# Dashboard_rev4.net
KiCad netlist of a schematic drawn in EAGLE
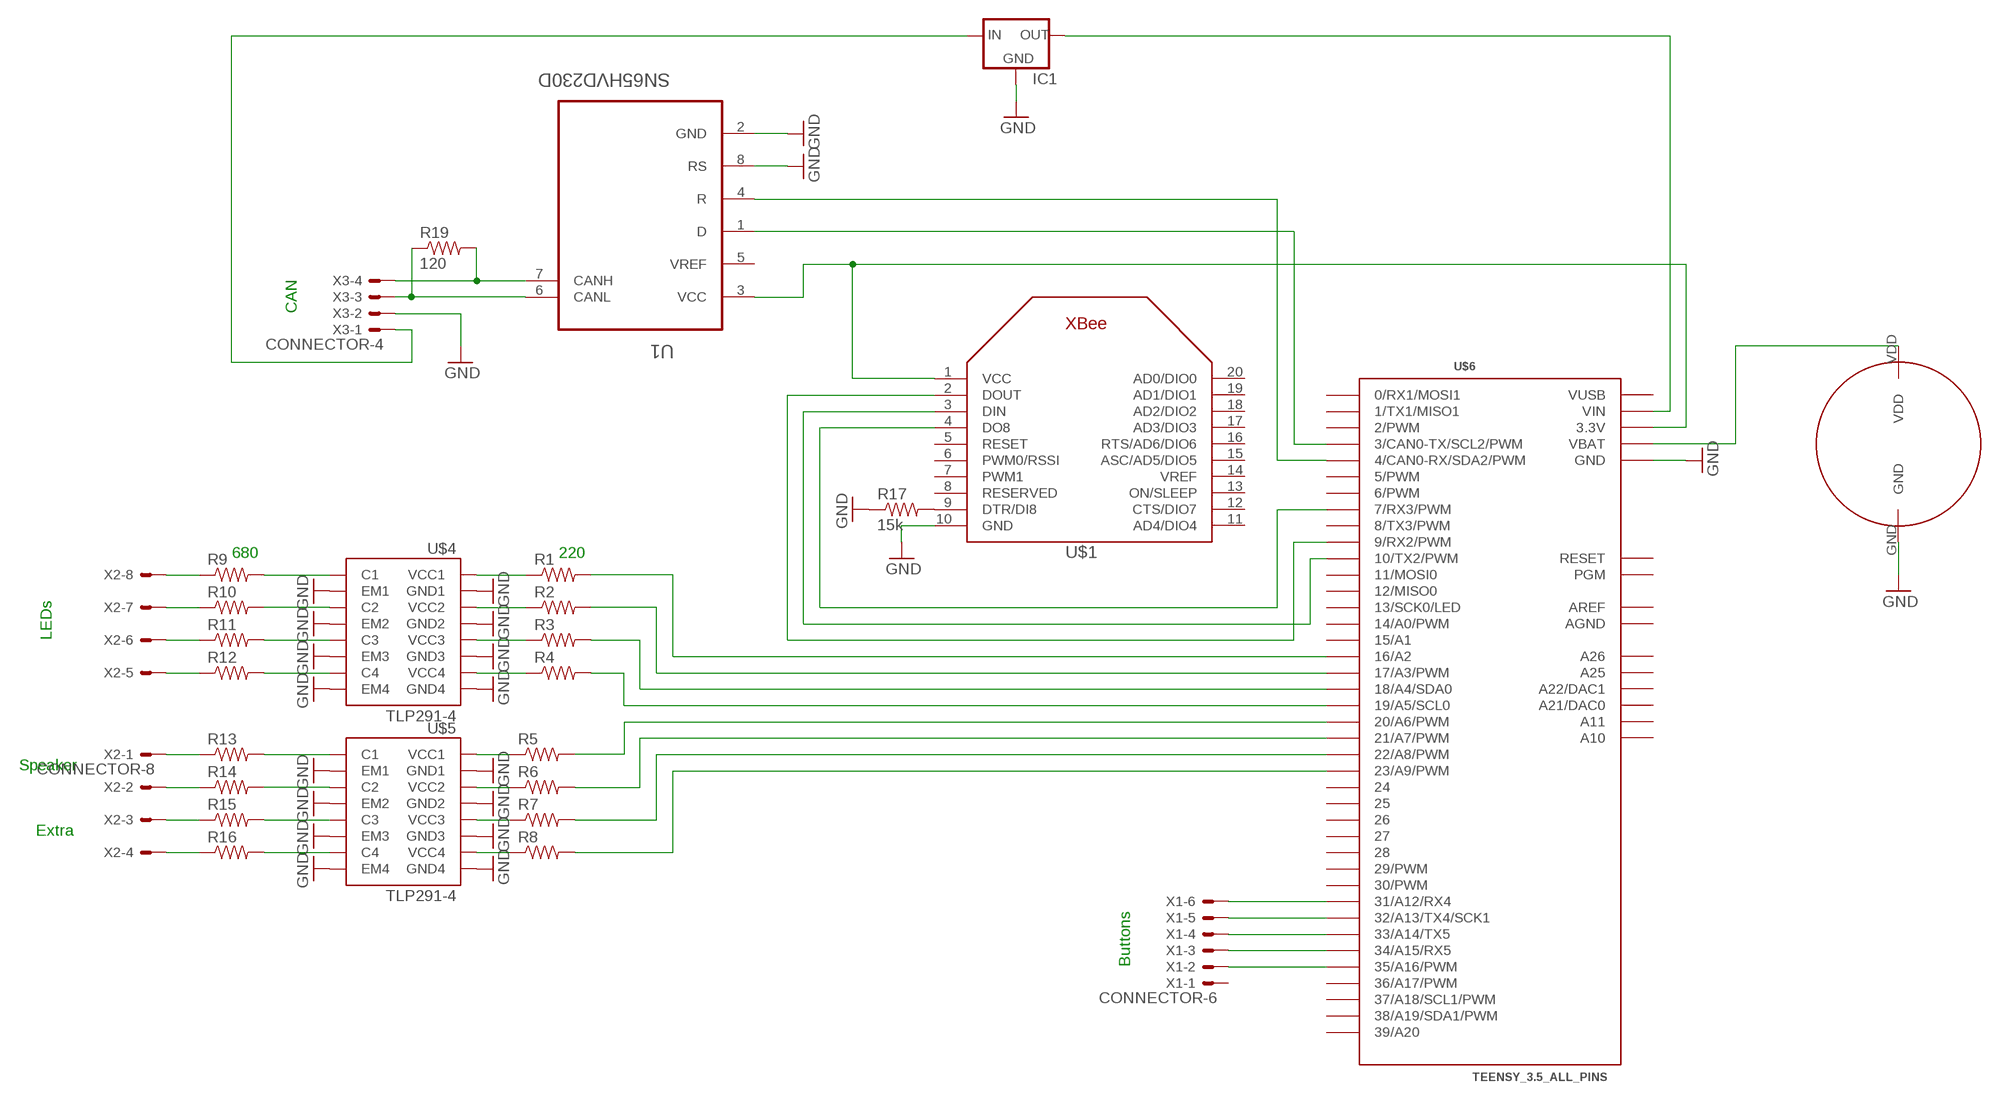
[diagram p0: schematic, sheet 1]

(export (version "E")
  (design (tool "Eeschema 10.0.6"))
  (components
    (comp (ref "IC1")
      (value "5VREG_L7805SPACED")
      (footprint "eagle-import:TO-220-SPACED")
      (libsource (lib "eagle-import") (part "5VREG_L7805SPACED"))
    )
    (comp (ref "R1")
      (value "RESISTORAXIAL-0.3")
      (footprint "eagle-import:AXIAL-0.3")
      (libsource (lib "eagle-import") (part "RESISTORAXIAL-0.3"))
    )
    (comp (ref "R2")
      (value "RESISTORAXIAL-0.3")
      (footprint "eagle-import:AXIAL-0.3")
      (libsource (lib "eagle-import") (part "RESISTORAXIAL-0.3"))
    )
    (comp (ref "R3")
      (value "RESISTORAXIAL-0.3")
      (footprint "eagle-import:AXIAL-0.3")
      (libsource (lib "eagle-import") (part "RESISTORAXIAL-0.3"))
    )
    (comp (ref "R4")
      (value "RESISTORAXIAL-0.3")
      (footprint "eagle-import:AXIAL-0.3")
      (libsource (lib "eagle-import") (part "RESISTORAXIAL-0.3"))
    )
    (comp (ref "R5")
      (value "RESISTORAXIAL-0.3")
      (footprint "eagle-import:AXIAL-0.3")
      (libsource (lib "eagle-import") (part "RESISTORAXIAL-0.3"))
    )
    (comp (ref "R6")
      (value "RESISTORAXIAL-0.3")
      (footprint "eagle-import:AXIAL-0.3")
      (libsource (lib "eagle-import") (part "RESISTORAXIAL-0.3"))
    )
    (comp (ref "R7")
      (value "RESISTORAXIAL-0.3")
      (footprint "eagle-import:AXIAL-0.3")
      (libsource (lib "eagle-import") (part "RESISTORAXIAL-0.3"))
    )
    (comp (ref "R8")
      (value "RESISTORAXIAL-0.3")
      (footprint "eagle-import:AXIAL-0.3")
      (libsource (lib "eagle-import") (part "RESISTORAXIAL-0.3"))
    )
    (comp (ref "R9")
      (value "RESISTORAXIAL-0.3")
      (footprint "eagle-import:AXIAL-0.3")
      (libsource (lib "eagle-import") (part "RESISTORAXIAL-0.3"))
    )
    (comp (ref "R10")
      (value "RESISTORAXIAL-0.3")
      (footprint "eagle-import:AXIAL-0.3")
      (libsource (lib "eagle-import") (part "RESISTORAXIAL-0.3"))
    )
    (comp (ref "R11")
      (value "RESISTORAXIAL-0.3")
      (footprint "eagle-import:AXIAL-0.3")
      (libsource (lib "eagle-import") (part "RESISTORAXIAL-0.3"))
    )
    (comp (ref "R12")
      (value "RESISTORAXIAL-0.3")
      (footprint "eagle-import:AXIAL-0.3")
      (libsource (lib "eagle-import") (part "RESISTORAXIAL-0.3"))
    )
    (comp (ref "R13")
      (value "RESISTORAXIAL-0.3")
      (footprint "eagle-import:AXIAL-0.3")
      (libsource (lib "eagle-import") (part "RESISTORAXIAL-0.3"))
    )
    (comp (ref "R14")
      (value "RESISTORAXIAL-0.3")
      (footprint "eagle-import:AXIAL-0.3")
      (libsource (lib "eagle-import") (part "RESISTORAXIAL-0.3"))
    )
    (comp (ref "R15")
      (value "RESISTORAXIAL-0.3")
      (footprint "eagle-import:AXIAL-0.3")
      (libsource (lib "eagle-import") (part "RESISTORAXIAL-0.3"))
    )
    (comp (ref "R16")
      (value "RESISTORAXIAL-0.3")
      (footprint "eagle-import:AXIAL-0.3")
      (libsource (lib "eagle-import") (part "RESISTORAXIAL-0.3"))
    )
    (comp (ref "R17")
      (value "15k")
      (footprint "eagle-import:AXIAL-0.3")
      (libsource (lib "eagle-import") (part "RESISTORAXIAL-0.3"))
    )
    (comp (ref "R19")
      (value "120")
      (footprint "eagle-import:AXIAL-0.3")
      (libsource (lib "eagle-import") (part "RESISTORAXIAL-0.3"))
    )
    (comp (ref "U$1")
      (value "XBEE")
      (footprint "eagle-import:XBEE")
      (libsource (lib "eagle-import") (part "XBEE"))
    )
    (comp (ref "U$2")
      (value "COIN-CELL-HOLDER")
      (footprint "eagle-import:COIN-CELL-HOLDER")
      (libsource (lib "eagle-import") (part "COIN-CELL-HOLDER"))
    )
    (comp (ref "U$4")
      (value "TLP291-4")
      (footprint "eagle-import:SOIC-16")
      (libsource (lib "eagle-import") (part "TLP291-4"))
    )
    (comp (ref "U$5")
      (value "TLP291-4")
      (footprint "eagle-import:SOIC-16")
      (libsource (lib "eagle-import") (part "TLP291-4"))
    )
    (comp (ref "U$6")
      (value "TEENSY_3.5_ALL_PINS")
      (footprint "eagle-import:TEENSY_3.5_ALL_PINS")
      (libsource (lib "eagle-import") (part "TEENSY_3.5_ALL_PINS"))
    )
    (comp (ref "U1")
      (value "SN65HVD230D")
      (footprint "eagle-import:SOIC127P600X175-8N")
      (libsource (lib "eagle-import") (part "SN65HVD230D"))
    )
    (comp (ref "X1")
      (value "CONNECTOR-6")
      (footprint "eagle-import:MINIFIT_5566-6")
      (fields (field (name "MPN") "95566-61002"))
      (libsource (lib "eagle-import") (part "CONNECTOR-6"))
    )
    (comp (ref "X2")
      (value "CONNECTOR-8")
      (footprint "eagle-import:MINIFIT_5566-8")
      (libsource (lib "eagle-import") (part "CONNECTOR-8"))
    )
    (comp (ref "X3")
      (value "CONNECTOR-4")
      (footprint "eagle-import:MINIFIT_5566-4")
      (libsource (lib "eagle-import") (part "CONNECTOR-4"))
    )
  )
  (nets
    (net (code "1") (name "/AGND") (class "Default")
      (node (ref "U$6") (pin "AGND") (pinfunction "AGND_AGND") (pintype "power_in"))
    )
    (net (code "2") (name "/AREF") (class "Default")
      (node (ref "U$6") (pin "AREF") (pinfunction "AREF_AREF") (pintype "power_in"))
    )
    (net (code "3") (name "/VUSB") (class "Default")
      (node (ref "U$6") (pin "VUSB") (pinfunction "VUSB_VUSB") (pintype "power_in"))
    )
    (net (code "4") (name "GND") (class "Default")
      (node (ref "IC1") (pin "2") (pinfunction "GND_2") (pintype "input"))
      (node (ref "R17") (pin "P$1") (pinfunction "1_P$1") (pintype "passive"))
      (node (ref "U$1") (pin "10") (pinfunction "GND_10") (pintype "power_in"))
      (node (ref "U$2") (pin "GND") (pinfunction "GND_GND") (pintype "bidirectional"))
      (node (ref "U$4") (pin "11") (pinfunction "EM3_11") (pintype "passive"))
      (node (ref "U$4") (pin "13") (pinfunction "EM2_13") (pintype "passive"))
      (node (ref "U$4") (pin "15") (pinfunction "EM1_15") (pintype "passive"))
      (node (ref "U$4") (pin "2") (pinfunction "GND1_2") (pintype "passive"))
      (node (ref "U$4") (pin "4") (pinfunction "GND2_4") (pintype "passive"))
      (node (ref "U$4") (pin "6") (pinfunction "GND3_6") (pintype "passive"))
      (node (ref "U$4") (pin "8") (pinfunction "GND4_8") (pintype "passive"))
      (node (ref "U$4") (pin "9") (pinfunction "EM4_9") (pintype "passive"))
      (node (ref "U$5") (pin "11") (pinfunction "EM3_11") (pintype "passive"))
      (node (ref "U$5") (pin "13") (pinfunction "EM2_13") (pintype "passive"))
      (node (ref "U$5") (pin "15") (pinfunction "EM1_15") (pintype "passive"))
      (node (ref "U$5") (pin "2") (pinfunction "GND1_2") (pintype "passive"))
      (node (ref "U$5") (pin "4") (pinfunction "GND2_4") (pintype "passive"))
      (node (ref "U$5") (pin "6") (pinfunction "GND3_6") (pintype "passive"))
      (node (ref "U$5") (pin "8") (pinfunction "GND4_8") (pintype "passive"))
      (node (ref "U$5") (pin "9") (pinfunction "EM4_9") (pintype "passive"))
      (node (ref "U$6") (pin "GND") (pinfunction "GND_GND") (pintype "power_in"))
      (node (ref "U$6") (pin "GND1") (pinfunction "GND_GND1") (pintype "power_in"))
      (node (ref "U$6") (pin "GND3") (pinfunction "GND_GND3") (pintype "power_in"))
      (node (ref "U$6") (pin "GND4") (pinfunction "GND_GND4") (pintype "power_in"))
      (node (ref "U$6") (pin "GND6") (pinfunction "GND_GND6") (pintype "power_in"))
      (node (ref "U1") (pin "2") (pinfunction "GND_2") (pintype "passive"))
      (node (ref "U1") (pin "8") (pinfunction "RS_8") (pintype "input"))
      (node (ref "X3") (pin "2") (pinfunction "S_2") (pintype "passive"))
    )
    (net (code "5") (name "Net-(IC1-IN)") (class "Default")
      (node (ref "IC1") (pin "1") (pinfunction "IN_1") (pintype "input"))
      (node (ref "X3") (pin "1") (pinfunction "S_1") (pintype "passive"))
    )
    (net (code "6") (name "Net-(IC1-OUT)") (class "Default")
      (node (ref "IC1") (pin "3") (pinfunction "OUT_3") (pintype "output"))
      (node (ref "U$6") (pin "VIN") (pinfunction "VIN_VIN") (pintype "power_in"))
    )
    (net (code "7") (name "Net-(R1-1)") (class "Default")
      (node (ref "R1") (pin "P$1") (pinfunction "1_P$1") (pintype "passive"))
      (node (ref "U$4") (pin "1") (pinfunction "VCC1_1") (pintype "passive"))
    )
    (net (code "8") (name "Net-(R1-2)") (class "Default")
      (node (ref "R1") (pin "P$2") (pinfunction "2_P$2") (pintype "passive"))
      (node (ref "U$6") (pin "16/A2") (pinfunction "16/A2_16/A2") (pintype "bidirectional"))
    )
    (net (code "9") (name "Net-(R2-1)") (class "Default")
      (node (ref "R2") (pin "P$1") (pinfunction "1_P$1") (pintype "passive"))
      (node (ref "U$4") (pin "3") (pinfunction "VCC2_3") (pintype "passive"))
    )
    (net (code "10") (name "Net-(R2-2)") (class "Default")
      (node (ref "R2") (pin "P$2") (pinfunction "2_P$2") (pintype "passive"))
      (node (ref "U$6") (pin "17/A3") (pinfunction "17/A3/PWM_17/A3") (pintype "bidirectional"))
    )
    (net (code "11") (name "Net-(R3-1)") (class "Default")
      (node (ref "R3") (pin "P$1") (pinfunction "1_P$1") (pintype "passive"))
      (node (ref "U$4") (pin "5") (pinfunction "VCC3_5") (pintype "passive"))
    )
    (net (code "12") (name "Net-(R3-2)") (class "Default")
      (node (ref "R3") (pin "P$2") (pinfunction "2_P$2") (pintype "passive"))
      (node (ref "U$6") (pin "18/A4") (pinfunction "18/A4/SDA0_18/A4") (pintype "bidirectional"))
    )
    (net (code "13") (name "Net-(R4-1)") (class "Default")
      (node (ref "R4") (pin "P$1") (pinfunction "1_P$1") (pintype "passive"))
      (node (ref "U$4") (pin "7") (pinfunction "VCC4_7") (pintype "passive"))
    )
    (net (code "14") (name "Net-(R4-2)") (class "Default")
      (node (ref "R4") (pin "P$2") (pinfunction "2_P$2") (pintype "passive"))
      (node (ref "U$6") (pin "19/A5") (pinfunction "19/A5/SCL0_19/A5") (pintype "bidirectional"))
    )
    (net (code "15") (name "Net-(R5-1)") (class "Default")
      (node (ref "R5") (pin "P$1") (pinfunction "1_P$1") (pintype "passive"))
      (node (ref "U$5") (pin "1") (pinfunction "VCC1_1") (pintype "passive"))
    )
    (net (code "16") (name "Net-(R5-2)") (class "Default")
      (node (ref "R5") (pin "P$2") (pinfunction "2_P$2") (pintype "passive"))
      (node (ref "U$6") (pin "20/A6") (pinfunction "20/A6/PWM_20/A6") (pintype "bidirectional"))
    )
    (net (code "17") (name "Net-(R6-1)") (class "Default")
      (node (ref "R6") (pin "P$1") (pinfunction "1_P$1") (pintype "passive"))
      (node (ref "U$5") (pin "3") (pinfunction "VCC2_3") (pintype "passive"))
    )
    (net (code "18") (name "Net-(R6-2)") (class "Default")
      (node (ref "R6") (pin "P$2") (pinfunction "2_P$2") (pintype "passive"))
      (node (ref "U$6") (pin "21/A7") (pinfunction "21/A7/PWM_21/A7") (pintype "bidirectional"))
    )
    (net (code "19") (name "Net-(R7-1)") (class "Default")
      (node (ref "R7") (pin "P$1") (pinfunction "1_P$1") (pintype "passive"))
      (node (ref "U$5") (pin "5") (pinfunction "VCC3_5") (pintype "passive"))
    )
    (net (code "20") (name "Net-(R7-2)") (class "Default")
      (node (ref "R7") (pin "P$2") (pinfunction "2_P$2") (pintype "passive"))
      (node (ref "U$6") (pin "22/A8") (pinfunction "22/A8/PWM_22/A8") (pintype "bidirectional"))
    )
    (net (code "21") (name "Net-(R8-1)") (class "Default")
      (node (ref "R8") (pin "P$1") (pinfunction "1_P$1") (pintype "passive"))
      (node (ref "U$5") (pin "7") (pinfunction "VCC4_7") (pintype "passive"))
    )
    (net (code "22") (name "Net-(R8-2)") (class "Default")
      (node (ref "R8") (pin "P$2") (pinfunction "2_P$2") (pintype "passive"))
      (node (ref "U$6") (pin "23/A9") (pinfunction "23/A9/PWM_23/A9") (pintype "bidirectional"))
    )
    (net (code "23") (name "Net-(R9-1)") (class "Default")
      (node (ref "R9") (pin "P$1") (pinfunction "1_P$1") (pintype "passive"))
      (node (ref "X2") (pin "8") (pinfunction "S_8") (pintype "passive"))
    )
    (net (code "24") (name "Net-(R9-2)") (class "Default")
      (node (ref "R9") (pin "P$2") (pinfunction "2_P$2") (pintype "passive"))
      (node (ref "U$4") (pin "16") (pinfunction "C1_16") (pintype "passive"))
    )
    (net (code "25") (name "Net-(R10-1)") (class "Default")
      (node (ref "R10") (pin "P$1") (pinfunction "1_P$1") (pintype "passive"))
      (node (ref "X2") (pin "7") (pinfunction "S_7") (pintype "passive"))
    )
    (net (code "26") (name "Net-(R10-2)") (class "Default")
      (node (ref "R10") (pin "P$2") (pinfunction "2_P$2") (pintype "passive"))
      (node (ref "U$4") (pin "14") (pinfunction "C2_14") (pintype "passive"))
    )
    (net (code "27") (name "Net-(R11-1)") (class "Default")
      (node (ref "R11") (pin "P$1") (pinfunction "1_P$1") (pintype "passive"))
      (node (ref "X2") (pin "6") (pinfunction "S_6") (pintype "passive"))
    )
    (net (code "28") (name "Net-(R11-2)") (class "Default")
      (node (ref "R11") (pin "P$2") (pinfunction "2_P$2") (pintype "passive"))
      (node (ref "U$4") (pin "12") (pinfunction "C3_12") (pintype "passive"))
    )
    (net (code "29") (name "Net-(R12-1)") (class "Default")
      (node (ref "R12") (pin "P$1") (pinfunction "1_P$1") (pintype "passive"))
      (node (ref "X2") (pin "5") (pinfunction "S_5") (pintype "passive"))
    )
    (net (code "30") (name "Net-(R12-2)") (class "Default")
      (node (ref "R12") (pin "P$2") (pinfunction "2_P$2") (pintype "passive"))
      (node (ref "U$4") (pin "10") (pinfunction "C4_10") (pintype "passive"))
    )
    (net (code "31") (name "Net-(R13-1)") (class "Default")
      (node (ref "R13") (pin "P$1") (pinfunction "1_P$1") (pintype "passive"))
      (node (ref "X2") (pin "1") (pinfunction "S_1") (pintype "passive"))
    )
    (net (code "32") (name "Net-(R13-2)") (class "Default")
      (node (ref "R13") (pin "P$2") (pinfunction "2_P$2") (pintype "passive"))
      (node (ref "U$5") (pin "16") (pinfunction "C1_16") (pintype "passive"))
    )
    (net (code "33") (name "Net-(R14-1)") (class "Default")
      (node (ref "R14") (pin "P$1") (pinfunction "1_P$1") (pintype "passive"))
      (node (ref "X2") (pin "2") (pinfunction "S_2") (pintype "passive"))
    )
    (net (code "34") (name "Net-(R14-2)") (class "Default")
      (node (ref "R14") (pin "P$2") (pinfunction "2_P$2") (pintype "passive"))
      (node (ref "U$5") (pin "14") (pinfunction "C2_14") (pintype "passive"))
    )
    (net (code "35") (name "Net-(R15-1)") (class "Default")
      (node (ref "R15") (pin "P$1") (pinfunction "1_P$1") (pintype "passive"))
      (node (ref "X2") (pin "3") (pinfunction "S_3") (pintype "passive"))
    )
    (net (code "36") (name "Net-(R15-2)") (class "Default")
      (node (ref "R15") (pin "P$2") (pinfunction "2_P$2") (pintype "passive"))
      (node (ref "U$5") (pin "12") (pinfunction "C3_12") (pintype "passive"))
    )
    (net (code "37") (name "Net-(R16-1)") (class "Default")
      (node (ref "R16") (pin "P$1") (pinfunction "1_P$1") (pintype "passive"))
      (node (ref "X2") (pin "4") (pinfunction "S_4") (pintype "passive"))
    )
    (net (code "38") (name "Net-(R16-2)") (class "Default")
      (node (ref "R16") (pin "P$2") (pinfunction "2_P$2") (pintype "passive"))
      (node (ref "U$5") (pin "10") (pinfunction "C4_10") (pintype "passive"))
    )
    (net (code "39") (name "Net-(R17-2)") (class "Default")
      (node (ref "R17") (pin "P$2") (pinfunction "2_P$2") (pintype "passive"))
      (node (ref "U$1") (pin "9") (pinfunction "DTR/DI8_9") (pintype "input"))
    )
    (net (code "40") (name "Net-(R19-1)") (class "Default")
      (node (ref "R19") (pin "P$1") (pinfunction "1_P$1") (pintype "passive"))
      (node (ref "U1") (pin "6") (pinfunction "CANL_6") (pintype "output"))
      (node (ref "X3") (pin "3") (pinfunction "S_3") (pintype "passive"))
    )
    (net (code "41") (name "Net-(R19-2)") (class "Default")
      (node (ref "R19") (pin "P$2") (pinfunction "2_P$2") (pintype "passive"))
      (node (ref "U1") (pin "7") (pinfunction "CANH_7") (pintype "output"))
      (node (ref "X3") (pin "4") (pinfunction "S_4") (pintype "passive"))
    )
    (net (code "42") (name "Net-(U$1-DIN)") (class "Default")
      (node (ref "U$1") (pin "3") (pinfunction "DIN_3") (pintype "input"))
      (node (ref "U$6") (pin "10") (pinfunction "10/TX2/PWM_10") (pintype "bidirectional"))
    )
    (net (code "43") (name "Net-(U$1-DO8)") (class "Default")
      (node (ref "U$1") (pin "4") (pinfunction "DO8_4") (pintype "output"))
      (node (ref "U$6") (pin "7") (pinfunction "7/RX3/PWM_7") (pintype "bidirectional"))
    )
    (net (code "44") (name "Net-(U$1-DOUT)") (class "Default")
      (node (ref "U$1") (pin "2") (pinfunction "DOUT_2") (pintype "output"))
      (node (ref "U$6") (pin "9") (pinfunction "9/RX2/PWM_9") (pintype "bidirectional"))
    )
    (net (code "45") (name "Net-(U$1-VCC)") (class "Default")
      (node (ref "U$1") (pin "1") (pinfunction "VCC_1") (pintype "power_in"))
      (node (ref "U$6") (pin "3.3V") (pinfunction "3.3V_3.3V") (pintype "power_in"))
      (node (ref "U$6") (pin "3.3V3") (pinfunction "3.3V_3.3V3") (pintype "power_in"))
      (node (ref "U$6") (pin "3.3V4") (pinfunction "3.3V_3.3V4") (pintype "power_in"))
      (node (ref "U1") (pin "3") (pinfunction "VCC_3") (pintype "power_in"))
    )
    (net (code "46") (name "Net-(U$2-PadVDD)") (class "Default")
      (node (ref "U$2") (pin "VDD") (pinfunction "VDD_VDD") (pintype "bidirectional"))
      (node (ref "U$6") (pin "VBAT") (pinfunction "VBAT_VBAT") (pintype "power_in"))
    )
    (net (code "47") (name "Net-(U$6-3{slash}CAN0-TX{slash}SCL2{slash}PWM)") (class "Default")
      (node (ref "U$6") (pin "3") (pinfunction "3/CAN0-TX/SCL2/PWM_3") (pintype "bidirectional"))
      (node (ref "U1") (pin "1") (pinfunction "D_1") (pintype "input"))
    )
    (net (code "48") (name "Net-(U$6-4{slash}CAN0-RX{slash}SDA2{slash}PWM)") (class "Default")
      (node (ref "U$6") (pin "4") (pinfunction "4/CAN0-RX/SDA2/PWM_4") (pintype "bidirectional"))
      (node (ref "U1") (pin "4") (pinfunction "R_4") (pintype "input"))
    )
    (net (code "49") (name "Net-(U$6-31{slash}A12{slash}RX4)") (class "Default")
      (node (ref "U$6") (pin "31/A12") (pinfunction "31/A12/RX4_31/A12") (pintype "bidirectional"))
      (node (ref "X1") (pin "6") (pinfunction "S_6") (pintype "passive"))
    )
    (net (code "50") (name "Net-(U$6-32{slash}A13{slash}TX4{slash}SCK1)") (class "Default")
      (node (ref "U$6") (pin "32/A13") (pinfunction "32/A13/TX4/SCK1_32/A13") (pintype "bidirectional"))
      (node (ref "X1") (pin "5") (pinfunction "S_5") (pintype "passive"))
    )
    (net (code "51") (name "Net-(U$6-33{slash}A14{slash}TX5)") (class "Default")
      (node (ref "U$6") (pin "33/A14") (pinfunction "33/A14/TX5_33/A14") (pintype "bidirectional"))
      (node (ref "X1") (pin "4") (pinfunction "S_4") (pintype "passive"))
    )
    (net (code "52") (name "Net-(U$6-34{slash}A15{slash}RX5)") (class "Default")
      (node (ref "U$6") (pin "34/A15") (pinfunction "34/A15/RX5_34/A15") (pintype "bidirectional"))
      (node (ref "X1") (pin "3") (pinfunction "S_3") (pintype "passive"))
    )
    (net (code "53") (name "Net-(U$6-35{slash}A16{slash}PWM)") (class "Default")
      (node (ref "U$6") (pin "35/A16") (pinfunction "35/A16/PWM_35/A16") (pintype "bidirectional"))
      (node (ref "X1") (pin "2") (pinfunction "S_2") (pintype "passive"))
    )
    (net (code "54") (name "unconnected-(U$1-AD0{slash}DIO0-Pad20)") (class "Default")
      (node (ref "U$1") (pin "20") (pinfunction "AD0/DIO0_20") (pintype "bidirectional"))
    )
    (net (code "55") (name "unconnected-(U$1-AD1{slash}DIO1-Pad19)") (class "Default")
      (node (ref "U$1") (pin "19") (pinfunction "AD1/DIO1_19") (pintype "bidirectional"))
    )
    (net (code "56") (name "unconnected-(U$1-AD2{slash}DIO2-Pad18)") (class "Default")
      (node (ref "U$1") (pin "18") (pinfunction "AD2/DIO2_18") (pintype "bidirectional"))
    )
    (net (code "57") (name "unconnected-(U$1-AD3{slash}DIO3-Pad17)") (class "Default")
      (node (ref "U$1") (pin "17") (pinfunction "AD3/DIO3_17") (pintype "bidirectional"))
    )
    (net (code "58") (name "unconnected-(U$1-AD4{slash}DIO4-Pad11)") (class "Default")
      (node (ref "U$1") (pin "11") (pinfunction "AD4/DIO4_11") (pintype "bidirectional"))
    )
    (net (code "59") (name "unconnected-(U$1-ASC{slash}AD5{slash}DIO5-Pad15)") (class "Default")
      (node (ref "U$1") (pin "15") (pinfunction "ASC/AD5/DIO5_15") (pintype "bidirectional"))
    )
    (net (code "60") (name "unconnected-(U$1-CTS{slash}DIO7-Pad12)") (class "Default")
      (node (ref "U$1") (pin "12") (pinfunction "CTS/DIO7_12") (pintype "bidirectional"))
    )
    (net (code "61") (name "unconnected-(U$1-ON{slash}SLEEP-Pad13)") (class "Default")
      (node (ref "U$1") (pin "13") (pinfunction "ON/SLEEP_13") (pintype "output"))
    )
    (net (code "62") (name "unconnected-(U$1-PWM0{slash}RSSI-Pad6)") (class "Default")
      (node (ref "U$1") (pin "6") (pinfunction "PWM0/RSSI_6") (pintype "output"))
    )
    (net (code "63") (name "unconnected-(U$1-PWM1-Pad7)") (class "Default")
      (node (ref "U$1") (pin "7") (pinfunction "PWM1_7") (pintype "output"))
    )
    (net (code "64") (name "unconnected-(U$1-RESERVED-Pad8)") (class "Default")
      (node (ref "U$1") (pin "8") (pinfunction "RESERVED_8") (pintype "no_connect"))
    )
    (net (code "65") (name "unconnected-(U$1-RESET-Pad5)") (class "Default")
      (node (ref "U$1") (pin "5") (pinfunction "RESET_5") (pintype "input"))
    )
    (net (code "66") (name "unconnected-(U$1-RTS{slash}AD6{slash}DIO6-Pad16)") (class "Default")
      (node (ref "U$1") (pin "16") (pinfunction "RTS/AD6/DIO6_16") (pintype "bidirectional"))
    )
    (net (code "67") (name "unconnected-(U$1-VREF-Pad14)") (class "Default")
      (node (ref "U$1") (pin "14") (pinfunction "VREF_14") (pintype "input"))
    )
    (net (code "68") (name "unconnected-(U$6-0{slash}RX1{slash}MOSI1-Pad0)") (class "Default")
      (node (ref "U$6") (pin "0") (pinfunction "0/RX1/MOSI1_0") (pintype "bidirectional"))
    )
    (net (code "69") (name "unconnected-(U$6-1{slash}TX1{slash}MISO1-Pad1)") (class "Default")
      (node (ref "U$6") (pin "1") (pinfunction "1/TX1/MISO1_1") (pintype "bidirectional"))
    )
    (net (code "70") (name "unconnected-(U$6-2{slash}PWM-Pad2)") (class "Default")
      (node (ref "U$6") (pin "2") (pinfunction "2/PWM_2") (pintype "bidirectional"))
    )
    (net (code "71") (name "unconnected-(U$6-5{slash}PWM-Pad5)") (class "Default")
      (node (ref "U$6") (pin "5") (pinfunction "5/PWM_5") (pintype "bidirectional"))
    )
    (net (code "72") (name "unconnected-(U$6-6{slash}PWM-Pad6)") (class "Default")
      (node (ref "U$6") (pin "6") (pinfunction "6/PWM_6") (pintype "bidirectional"))
    )
    (net (code "73") (name "unconnected-(U$6-8{slash}TX3{slash}PWM-Pad8)") (class "Default")
      (node (ref "U$6") (pin "8") (pinfunction "8/TX3/PWM_8") (pintype "bidirectional"))
    )
    (net (code "74") (name "unconnected-(U$6-11{slash}MOSI0-Pad11)") (class "Default")
      (node (ref "U$6") (pin "11") (pinfunction "11/MOSI0_11") (pintype "bidirectional"))
    )
    (net (code "75") (name "unconnected-(U$6-12{slash}MISO0-Pad12)") (class "Default")
      (node (ref "U$6") (pin "12") (pinfunction "12/MISO0_12") (pintype "bidirectional"))
    )
    (net (code "76") (name "unconnected-(U$6-13{slash}SCK0{slash}LED-Pad13)") (class "Default")
      (node (ref "U$6") (pin "13") (pinfunction "13/SCK0/LED_13") (pintype "bidirectional"))
    )
    (net (code "77") (name "unconnected-(U$6-14{slash}A0{slash}PWM-Pad14{slash}A0)") (class "Default")
      (node (ref "U$6") (pin "14/A0") (pinfunction "14/A0/PWM_14/A0") (pintype "bidirectional"))
    )
    (net (code "78") (name "unconnected-(U$6-29{slash}PWM-Pad29)") (class "Default")
      (node (ref "U$6") (pin "29") (pinfunction "29/PWM_29") (pintype "bidirectional"))
    )
    (net (code "79") (name "unconnected-(U$6-30{slash}PWM-Pad30)") (class "Default")
      (node (ref "U$6") (pin "30") (pinfunction "30/PWM_30") (pintype "bidirectional"))
    )
    (net (code "80") (name "unconnected-(U$6-36{slash}A17{slash}PWM-Pad36{slash}A17)") (class "Default")
      (node (ref "U$6") (pin "36/A17") (pinfunction "36/A17/PWM_36/A17") (pintype "bidirectional"))
    )
    (net (code "81") (name "unconnected-(U$6-37{slash}A18{slash}SCL1{slash}PWM-Pad37{slash}A18)") (class "Default")
      (node (ref "U$6") (pin "37/A18") (pinfunction "37/A18/SCL1/PWM_37/A18") (pintype "bidirectional"))
    )
    (net (code "82") (name "unconnected-(U$6-38{slash}A19{slash}SDA1{slash}PWM-Pad38{slash}A19)") (class "Default")
      (node (ref "U$6") (pin "38/A19") (pinfunction "38/A19/SDA1/PWM_38/A19") (pintype "bidirectional"))
    )
    (net (code "83") (name "unconnected-(U$6-A21{slash}DAC0-PadA21)") (class "Default")
      (node (ref "U$6") (pin "A21") (pinfunction "A21/DAC0_A21") (pintype "bidirectional"))
    )
    (net (code "84") (name "unconnected-(U$6-A22{slash}DAC1-PadA22)") (class "Default")
      (node (ref "U$6") (pin "A22") (pinfunction "A22/DAC1_A22") (pintype "bidirectional"))
    )
    (net (code "85") (name "unconnected-(U$6-Pad15{slash}A1)") (class "Default")
      (node (ref "U$6") (pin "15/A1") (pinfunction "15/A1_15/A1") (pintype "bidirectional"))
    )
    (net (code "86") (name "unconnected-(U$6-Pad24)") (class "Default")
      (node (ref "U$6") (pin "24") (pinfunction "24_24") (pintype "bidirectional"))
    )
    (net (code "87") (name "unconnected-(U$6-Pad25)") (class "Default")
      (node (ref "U$6") (pin "25") (pinfunction "25_25") (pintype "bidirectional"))
    )
    (net (code "88") (name "unconnected-(U$6-Pad26)") (class "Default")
      (node (ref "U$6") (pin "26") (pinfunction "26_26") (pintype "bidirectional"))
    )
    (net (code "89") (name "unconnected-(U$6-Pad27)") (class "Default")
      (node (ref "U$6") (pin "27") (pinfunction "27_27") (pintype "bidirectional"))
    )
    (net (code "90") (name "unconnected-(U$6-Pad28)") (class "Default")
      (node (ref "U$6") (pin "28") (pinfunction "28_28") (pintype "bidirectional"))
    )
    (net (code "91") (name "unconnected-(U$6-Pad39{slash}A20)") (class "Default")
      (node (ref "U$6") (pin "39/A20") (pinfunction "39/A20_39/A20") (pintype "bidirectional"))
    )
    (net (code "92") (name "unconnected-(U$6-PadA10)") (class "Default")
      (node (ref "U$6") (pin "A10") (pinfunction "A10_A10") (pintype "bidirectional"))
    )
    (net (code "93") (name "unconnected-(U$6-PadA11)") (class "Default")
      (node (ref "U$6") (pin "A11") (pinfunction "A11_A11") (pintype "bidirectional"))
    )
    (net (code "94") (name "unconnected-(U$6-PadA25)") (class "Default")
      (node (ref "U$6") (pin "A25") (pinfunction "A25_A25") (pintype "bidirectional"))
    )
    (net (code "95") (name "unconnected-(U$6-PadA26)") (class "Default")
      (node (ref "U$6") (pin "A26") (pinfunction "A26_A26") (pintype "bidirectional"))
    )
    (net (code "96") (name "unconnected-(U$6-PadPGM)") (class "Default")
      (node (ref "U$6") (pin "PGM") (pinfunction "PGM_PGM") (pintype "bidirectional"))
    )
    (net (code "97") (name "unconnected-(U$6-PadRESET)") (class "Default")
      (node (ref "U$6") (pin "RESET") (pinfunction "RESET_RESET") (pintype "bidirectional"))
    )
    (net (code "98") (name "unconnected-(U1-VREF-Pad5)") (class "Default")
      (node (ref "U1") (pin "5") (pinfunction "VREF_5") (pintype "input"))
    )
    (net (code "99") (name "unconnected-(X1A-S-Pad1)") (class "Default")
      (node (ref "X1") (pin "1") (pinfunction "S_1") (pintype "passive"))
    )
  )
)
